# edge_dff.net
KiCad netlist of a schematic drawn in Altium Designer
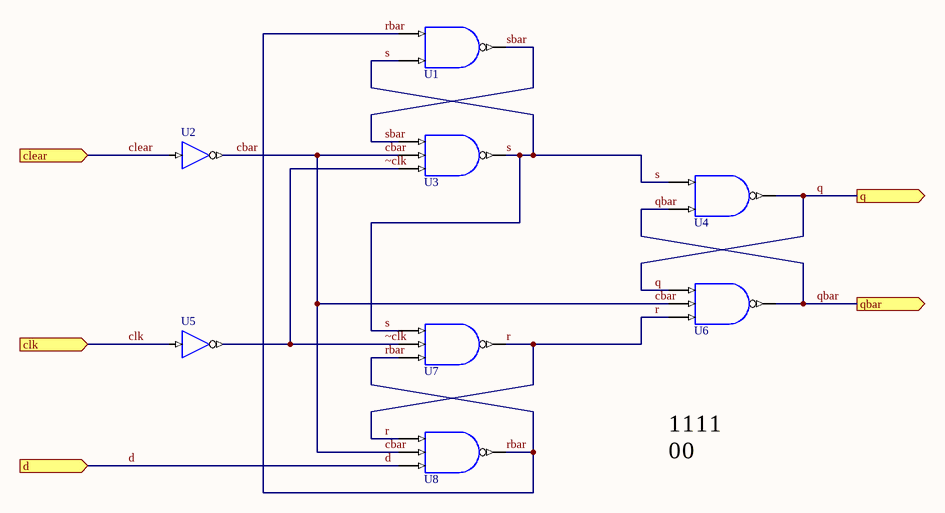
[diagram p0: edge_dff.SchDoc]

(export (version "E")
  (design (tool "Eeschema 10.0.6"))
  (components
    (comp (ref "U1")
      (value "AND 2")
      (description "2 Input AND")
      (libsource (lib "BlockSchematics") (part "AND_2"))
    )
    (comp (ref "U2")
      (value "BUF_inv")
      (description "1-bit General Purpose (Non-inverting) Buffer")
      (libsource (lib "BlockSchematics") (part "BUF_inv"))
    )
    (comp (ref "U3")
      (value "NAND_3")
      (description "3 Input NAND 1 Not")
      (libsource (lib "BlockSchematics") (part "NAND_3"))
    )
    (comp (ref "U4")
      (value "AND 2")
      (description "2 Input AND")
      (libsource (lib "BlockSchematics") (part "AND_2"))
    )
    (comp (ref "U5")
      (value "BUF_inv")
      (description "1-bit General Purpose (Non-inverting) Buffer")
      (libsource (lib "BlockSchematics") (part "BUF_inv"))
    )
    (comp (ref "U6")
      (value "NAND_3")
      (description "3 Input NAND 1 Not")
      (libsource (lib "BlockSchematics") (part "NAND_3"))
    )
    (comp (ref "U7")
      (value "NAND_3")
      (description "3 Input NAND 1 Not")
      (libsource (lib "BlockSchematics") (part "NAND_3"))
    )
    (comp (ref "U8")
      (value "NAND_3")
      (description "3 Input NAND 1 Not")
      (libsource (lib "BlockSchematics") (part "NAND_3"))
    )
  )
  (nets
    (net (code "1") (name "/cbar") (class "Default")
      (node (ref "U2") (pin "O") (pinfunction "O_O") (pintype "output"))
      (node (ref "U3") (pin "B") (pinfunction "B_B") (pintype "input"))
      (node (ref "U6") (pin "B") (pinfunction "B_B") (pintype "input"))
      (node (ref "U8") (pin "B") (pinfunction "B_B") (pintype "input"))
    )
    (net (code "2") (name "/clear") (class "Default")
      (node (ref "U2") (pin "I") (pinfunction "I_I") (pintype "input"))
    )
    (net (code "3") (name "/clk") (class "Default")
      (node (ref "U5") (pin "I") (pinfunction "I_I") (pintype "input"))
    )
    (net (code "4") (name "/d") (class "Default")
      (node (ref "U8") (pin "C") (pinfunction "C_C") (pintype "input"))
    )
    (net (code "5") (name "/q") (class "Default")
      (node (ref "U4") (pin "Y") (pinfunction "Y_Y") (pintype "output"))
      (node (ref "U6") (pin "A") (pinfunction "A_A") (pintype "input"))
    )
    (net (code "6") (name "/qbar") (class "Default")
      (node (ref "U4") (pin "B") (pinfunction "B_B") (pintype "input"))
      (node (ref "U6") (pin "Y") (pinfunction "Y_Y") (pintype "output"))
    )
    (net (code "7") (name "/r") (class "Default")
      (node (ref "U6") (pin "C") (pinfunction "C_C") (pintype "input"))
      (node (ref "U7") (pin "Y") (pinfunction "Y_Y") (pintype "output"))
      (node (ref "U8") (pin "A") (pinfunction "A_A") (pintype "input"))
    )
    (net (code "8") (name "/rbar") (class "Default")
      (node (ref "U1") (pin "A") (pinfunction "A_A") (pintype "input"))
      (node (ref "U7") (pin "C") (pinfunction "C_C") (pintype "input"))
      (node (ref "U8") (pin "Y") (pinfunction "Y_Y") (pintype "output"))
    )
    (net (code "9") (name "/s") (class "Default")
      (node (ref "U1") (pin "B") (pinfunction "B_B") (pintype "input"))
      (node (ref "U3") (pin "Y") (pinfunction "Y_Y") (pintype "output"))
      (node (ref "U4") (pin "A") (pinfunction "A_A") (pintype "input"))
      (node (ref "U7") (pin "A") (pinfunction "A_A") (pintype "input"))
    )
    (net (code "10") (name "/sbar") (class "Default")
      (node (ref "U1") (pin "Y") (pinfunction "Y_Y") (pintype "output"))
      (node (ref "U3") (pin "A") (pinfunction "A_A") (pintype "input"))
    )
    (net (code "11") (name "/~clk") (class "Default")
      (node (ref "U3") (pin "C") (pinfunction "C_C") (pintype "input"))
      (node (ref "U5") (pin "O") (pinfunction "O_O") (pintype "output"))
      (node (ref "U7") (pin "B") (pinfunction "B_B") (pintype "input"))
    )
  )
)
